# DRAM_DDR4.net
KiCad netlist of a schematic drawn in Altium Designer
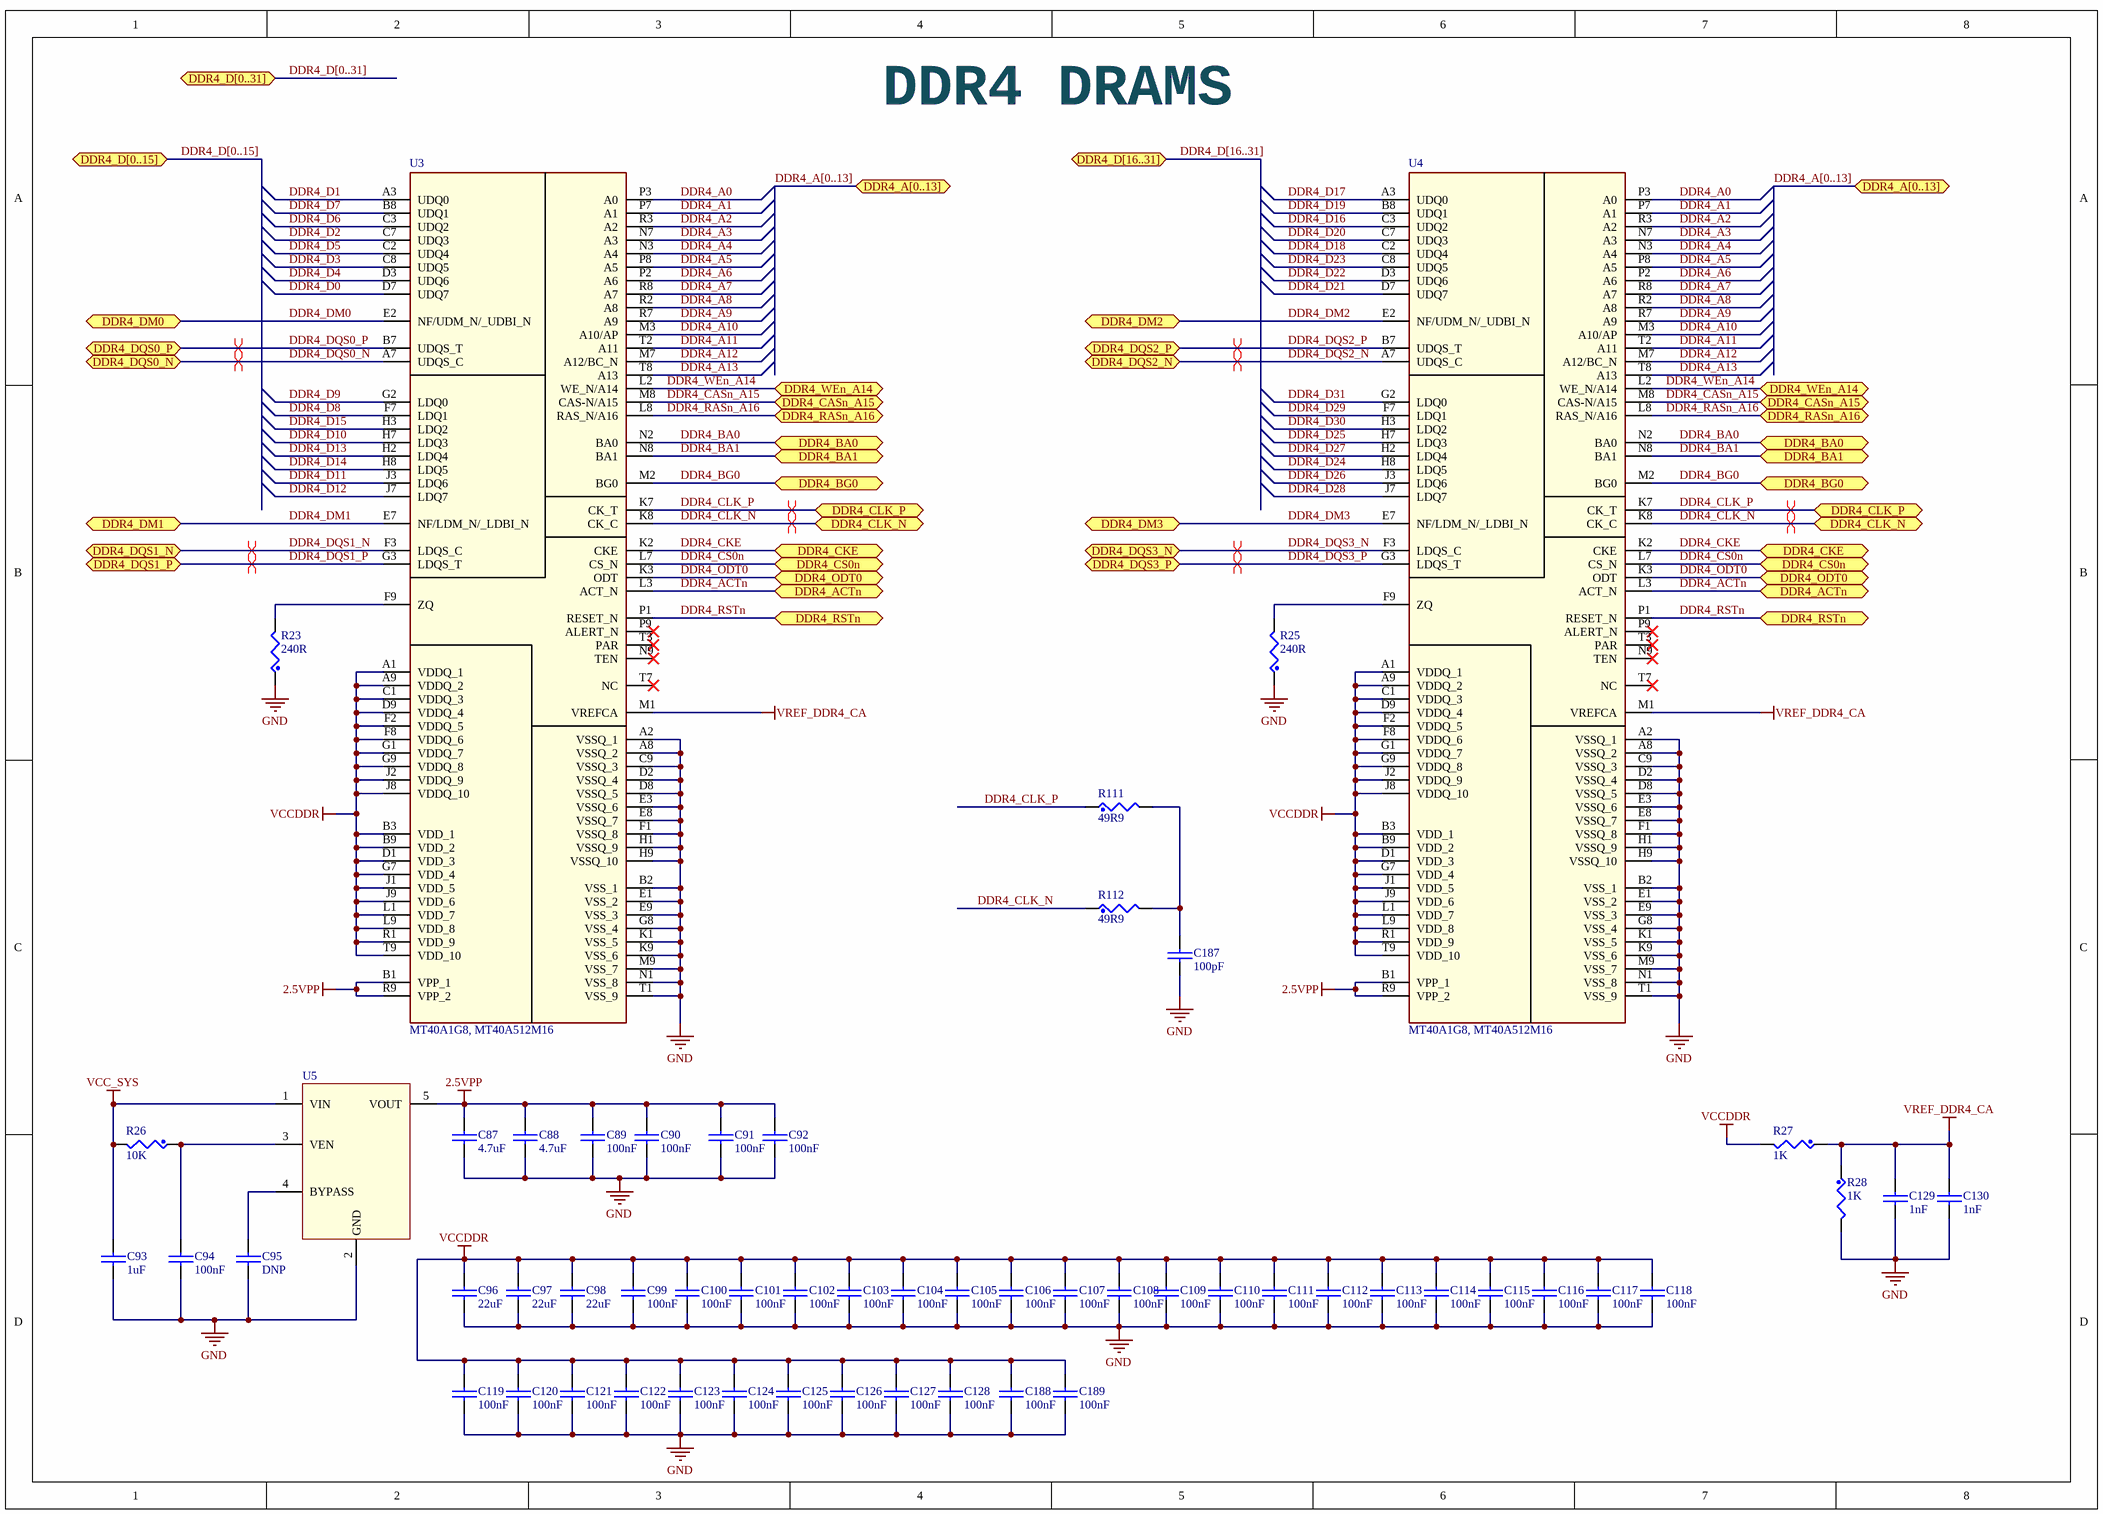
[diagram p0: DRAM_DDR4.SchDoc]

(export (version "E")
  (design (tool "Eeschema 10.0.6"))
  (components
    (comp (ref "C87")
      (value "4.7uF")
      (footprint "0402_CC - C")
      (libsource (lib "AAR_RockChip_RK3328") (part "CAP_NP"))
    )
    (comp (ref "C88")
      (value "4.7uF")
      (footprint "0402_CC - C")
      (libsource (lib "AAR_RockChip_RK3328") (part "CAP_NP"))
    )
    (comp (ref "C89")
      (value "100nF")
      (footprint "0402_CC - C")
      (libsource (lib "AAR_RockChip_RK3328") (part "CAP_NP"))
    )
    (comp (ref "C90")
      (value "100nF")
      (footprint "0402_CC - C")
      (libsource (lib "AAR_RockChip_RK3328") (part "CAP_NP"))
    )
    (comp (ref "C91")
      (value "100nF")
      (footprint "0402_CC - C")
      (libsource (lib "AAR_RockChip_RK3328") (part "CAP_NP"))
    )
    (comp (ref "C92")
      (value "100nF")
      (footprint "0402_CC - C")
      (libsource (lib "AAR_RockChip_RK3328") (part "CAP_NP"))
    )
    (comp (ref "C93")
      (value "1uF")
      (footprint "0402_CC - C")
      (libsource (lib "AAR_RockChip_RK3328") (part "CAP_NP"))
    )
    (comp (ref "C94")
      (value "100nF")
      (footprint "0402_CC - C")
      (libsource (lib "AAR_RockChip_RK3328") (part "CAP_NP"))
    )
    (comp (ref "C95")
      (value "DNP")
      (footprint "0402_CC - C")
      (libsource (lib "AAR_RockChip_RK3328") (part "CAP_NP"))
    )
    (comp (ref "C96")
      (value "22uF")
      (footprint "0603_CC")
      (libsource (lib "AAR_RockChip_RK3328") (part "CAP_NP"))
    )
    (comp (ref "C97")
      (value "22uF")
      (footprint "0603_CC")
      (libsource (lib "AAR_RockChip_RK3328") (part "CAP_NP"))
    )
    (comp (ref "C98")
      (value "22uF")
      (footprint "0603_CC")
      (libsource (lib "AAR_RockChip_RK3328") (part "CAP_NP"))
    )
    (comp (ref "C99")
      (value "100nF")
      (footprint "0402_CC - C")
      (libsource (lib "AAR_RockChip_RK3328") (part "CAP_NP"))
    )
    (comp (ref "C100")
      (value "100nF")
      (footprint "0402_CC - C")
      (libsource (lib "AAR_RockChip_RK3328") (part "CAP_NP"))
    )
    (comp (ref "C101")
      (value "100nF")
      (footprint "0402_CC - C")
      (libsource (lib "AAR_RockChip_RK3328") (part "CAP_NP"))
    )
    (comp (ref "C102")
      (value "100nF")
      (footprint "0402_CC - C")
      (libsource (lib "AAR_RockChip_RK3328") (part "CAP_NP"))
    )
    (comp (ref "C103")
      (value "100nF")
      (footprint "0402_CC - C")
      (libsource (lib "AAR_RockChip_RK3328") (part "CAP_NP"))
    )
    (comp (ref "C104")
      (value "100nF")
      (footprint "0402_CC - C")
      (libsource (lib "AAR_RockChip_RK3328") (part "CAP_NP"))
    )
    (comp (ref "C105")
      (value "100nF")
      (footprint "0402_CC - C")
      (libsource (lib "AAR_RockChip_RK3328") (part "CAP_NP"))
    )
    (comp (ref "C106")
      (value "100nF")
      (footprint "0402_CC - C")
      (libsource (lib "AAR_RockChip_RK3328") (part "CAP_NP"))
    )
    (comp (ref "C107")
      (value "100nF")
      (footprint "0402_CC - C")
      (libsource (lib "AAR_RockChip_RK3328") (part "CAP_NP"))
    )
    (comp (ref "C108")
      (value "100nF")
      (footprint "0402_CC - C")
      (libsource (lib "AAR_RockChip_RK3328") (part "CAP_NP"))
    )
    (comp (ref "C109")
      (value "100nF")
      (footprint "0402_CC - C")
      (libsource (lib "AAR_RockChip_RK3328") (part "CAP_NP"))
    )
    (comp (ref "C110")
      (value "100nF")
      (footprint "0402_CC - C")
      (libsource (lib "AAR_RockChip_RK3328") (part "CAP_NP"))
    )
    (comp (ref "C111")
      (value "100nF")
      (footprint "0402_CC - C")
      (libsource (lib "AAR_RockChip_RK3328") (part "CAP_NP"))
    )
    (comp (ref "C112")
      (value "100nF")
      (footprint "0402_CC - C")
      (libsource (lib "AAR_RockChip_RK3328") (part "CAP_NP"))
    )
    (comp (ref "C113")
      (value "100nF")
      (footprint "0402_CC - C")
      (libsource (lib "AAR_RockChip_RK3328") (part "CAP_NP"))
    )
    (comp (ref "C114")
      (value "100nF")
      (footprint "0402_CC - C")
      (libsource (lib "AAR_RockChip_RK3328") (part "CAP_NP"))
    )
    (comp (ref "C115")
      (value "100nF")
      (footprint "0402_CC - C")
      (libsource (lib "AAR_RockChip_RK3328") (part "CAP_NP"))
    )
    (comp (ref "C116")
      (value "100nF")
      (footprint "0402_CC - C")
      (libsource (lib "AAR_RockChip_RK3328") (part "CAP_NP"))
    )
    (comp (ref "C117")
      (value "100nF")
      (footprint "0402_CC - C")
      (libsource (lib "AAR_RockChip_RK3328") (part "CAP_NP"))
    )
    (comp (ref "C118")
      (value "100nF")
      (footprint "0402_CC - C")
      (libsource (lib "AAR_RockChip_RK3328") (part "CAP_NP"))
    )
    (comp (ref "C119")
      (value "100nF")
      (footprint "0402_CC - C")
      (libsource (lib "AAR_RockChip_RK3328") (part "CAP_NP"))
    )
    (comp (ref "C120")
      (value "100nF")
      (footprint "0402_CC - C")
      (libsource (lib "AAR_RockChip_RK3328") (part "CAP_NP"))
    )
    (comp (ref "C121")
      (value "100nF")
      (footprint "0402_CC - C")
      (libsource (lib "AAR_RockChip_RK3328") (part "CAP_NP"))
    )
    (comp (ref "C122")
      (value "100nF")
      (footprint "0402_CC - C")
      (libsource (lib "AAR_RockChip_RK3328") (part "CAP_NP"))
    )
    (comp (ref "C123")
      (value "100nF")
      (footprint "0402_CC - C")
      (libsource (lib "AAR_RockChip_RK3328") (part "CAP_NP"))
    )
    (comp (ref "C124")
      (value "100nF")
      (footprint "0402_CC - C")
      (libsource (lib "AAR_RockChip_RK3328") (part "CAP_NP"))
    )
    (comp (ref "C125")
      (value "100nF")
      (footprint "0402_CC - C")
      (libsource (lib "AAR_RockChip_RK3328") (part "CAP_NP"))
    )
    (comp (ref "C126")
      (value "100nF")
      (footprint "0402_CC - C")
      (libsource (lib "AAR_RockChip_RK3328") (part "CAP_NP"))
    )
    (comp (ref "C127")
      (value "100nF")
      (footprint "0402_CC - C")
      (libsource (lib "AAR_RockChip_RK3328") (part "CAP_NP"))
    )
    (comp (ref "C128")
      (value "100nF")
      (footprint "0402_CC - C")
      (libsource (lib "AAR_RockChip_RK3328") (part "CAP_NP"))
    )
    (comp (ref "C129")
      (value "1nF")
      (footprint "0402_CC - C")
      (libsource (lib "AAR_RockChip_RK3328") (part "CAP_NP"))
    )
    (comp (ref "C130")
      (value "1nF")
      (footprint "0402_CC - C")
      (libsource (lib "AAR_RockChip_RK3328") (part "CAP_NP"))
    )
    (comp (ref "C187")
      (value "100pF")
      (footprint "0402_CC - C")
      (libsource (lib "AAR_RockChip_RK3328") (part "CAP_NP"))
    )
    (comp (ref "C188")
      (value "100nF")
      (footprint "0402_CC - C")
      (libsource (lib "AAR_RockChip_RK3328") (part "CAP_NP"))
    )
    (comp (ref "C189")
      (value "100nF")
      (footprint "0402_CC - C")
      (libsource (lib "AAR_RockChip_RK3328") (part "CAP_NP"))
    )
    (comp (ref "R23")
      (value "240R")
      (footprint "0402_CR")
      (libsource (lib "AAR_RockChip_RK3328") (part "RES"))
    )
    (comp (ref "R25")
      (value "240R")
      (footprint "0402_CR")
      (libsource (lib "AAR_RockChip_RK3328") (part "RES"))
    )
    (comp (ref "R26")
      (value "10K")
      (footprint "0402_CR")
      (libsource (lib "AAR_RockChip_RK3328") (part "RES"))
    )
    (comp (ref "R27") (value "1K") (footprint "0603_CR") (libsource (lib "AAR_RockChip_RK3328") (part "RES")))
    (comp (ref "R28") (value "1K") (footprint "0603_CR") (libsource (lib "AAR_RockChip_RK3328") (part "RES")))
    (comp (ref "R111")
      (value "49R9")
      (footprint "0402_CR")
      (libsource (lib "AAR_RockChip_RK3328") (part "RES"))
    )
    (comp (ref "R112")
      (value "49R9")
      (footprint "0402_CR")
      (libsource (lib "AAR_RockChip_RK3328") (part "RES"))
    )
    (comp (ref "U3")
      (value "MT40A1G8, MT40A512M16")
      (footprint "BGA96C80P9X16_1000X1400X120")
      (description "AAR, MT40A, DDR4 , 96-Ball x16")
      (fields (field (name "MANUFACTURER_PART_NUMBER") "MT40A1G16HBA-083E"))
      (libsource (lib "AAR_RockChip_RK3328") (part "MT40A1G8"))
    )
    (comp (ref "U4")
      (value "MT40A1G8, MT40A512M16")
      (footprint "BGA96C80P9X16_1000X1400X120")
      (description "AAR, MT40A, DDR4 , 96-Ball x16")
      (fields (field (name "MANUFACTURER_PART_NUMBER") "MT40A1G16HBA-083E"))
      (libsource (lib "AAR_RockChip_RK3328") (part "MT40A1G8"))
    )
    (comp (ref "U5")
      (value "LDO")
      (footprint "SOT23_5")
      (description "PT5108  , High-PSRR 500mA LDO, By AAR")
      (libsource (lib "AAR_RockChip_RK3328") (part "PT5108"))
    )
  )
  (nets
    (net (code "1") (name "/DDR4_A0") (class "Default")
      (node (ref "U3") (pin "P3") (pinfunction "A0_P3") (pintype "passive"))
      (node (ref "U4") (pin "P3") (pinfunction "A0_P3") (pintype "passive"))
    )
    (net (code "2") (name "/DDR4_A1") (class "Default")
      (node (ref "U3") (pin "P7") (pinfunction "A1_P7") (pintype "passive"))
      (node (ref "U4") (pin "P7") (pinfunction "A1_P7") (pintype "passive"))
    )
    (net (code "3") (name "/DDR4_A2") (class "Default")
      (node (ref "U3") (pin "R3") (pinfunction "A2_R3") (pintype "passive"))
      (node (ref "U4") (pin "R3") (pinfunction "A2_R3") (pintype "passive"))
    )
    (net (code "4") (name "/DDR4_A3") (class "Default")
      (node (ref "U3") (pin "N7") (pinfunction "A3_N7") (pintype "passive"))
      (node (ref "U4") (pin "N7") (pinfunction "A3_N7") (pintype "passive"))
    )
    (net (code "5") (name "/DDR4_A4") (class "Default")
      (node (ref "U3") (pin "N3") (pinfunction "A4_N3") (pintype "passive"))
      (node (ref "U4") (pin "N3") (pinfunction "A4_N3") (pintype "passive"))
    )
    (net (code "6") (name "/DDR4_A5") (class "Default")
      (node (ref "U3") (pin "P8") (pinfunction "A5_P8") (pintype "passive"))
      (node (ref "U4") (pin "P8") (pinfunction "A5_P8") (pintype "passive"))
    )
    (net (code "7") (name "/DDR4_A6") (class "Default")
      (node (ref "U3") (pin "P2") (pinfunction "A6_P2") (pintype "passive"))
      (node (ref "U4") (pin "P2") (pinfunction "A6_P2") (pintype "passive"))
    )
    (net (code "8") (name "/DDR4_A7") (class "Default")
      (node (ref "U3") (pin "R8") (pinfunction "A7_R8") (pintype "passive"))
      (node (ref "U4") (pin "R8") (pinfunction "A7_R8") (pintype "passive"))
    )
    (net (code "9") (name "/DDR4_A8") (class "Default")
      (node (ref "U3") (pin "R2") (pinfunction "A8_R2") (pintype "passive"))
      (node (ref "U4") (pin "R2") (pinfunction "A8_R2") (pintype "passive"))
    )
    (net (code "10") (name "/DDR4_A9") (class "Default")
      (node (ref "U3") (pin "R7") (pinfunction "A9_R7") (pintype "passive"))
      (node (ref "U4") (pin "R7") (pinfunction "A9_R7") (pintype "passive"))
    )
    (net (code "11") (name "/DDR4_A10") (class "Default")
      (node (ref "U3") (pin "M3") (pinfunction "A10/AP_M3") (pintype "passive"))
      (node (ref "U4") (pin "M3") (pinfunction "A10/AP_M3") (pintype "passive"))
    )
    (net (code "12") (name "/DDR4_A11") (class "Default")
      (node (ref "U3") (pin "T2") (pinfunction "A11_T2") (pintype "passive"))
      (node (ref "U4") (pin "T2") (pinfunction "A11_T2") (pintype "passive"))
    )
    (net (code "13") (name "/DDR4_A12") (class "Default")
      (node (ref "U3") (pin "M7") (pinfunction "A12/BC_N_M7") (pintype "passive"))
      (node (ref "U4") (pin "M7") (pinfunction "A12/BC_N_M7") (pintype "passive"))
    )
    (net (code "14") (name "/DDR4_A13") (class "Default")
      (node (ref "U3") (pin "T8") (pinfunction "A13_T8") (pintype "passive"))
      (node (ref "U4") (pin "T8") (pinfunction "A13_T8") (pintype "passive"))
    )
    (net (code "15") (name "/DDR4_ACTn") (class "Default")
      (node (ref "U3") (pin "L3") (pinfunction "ACT_N_L3") (pintype "passive"))
      (node (ref "U4") (pin "L3") (pinfunction "ACT_N_L3") (pintype "passive"))
    )
    (net (code "17") (name "/DDR4_BA0") (class "Default")
      (node (ref "U3") (pin "N2") (pinfunction "BA0_N2") (pintype "passive"))
      (node (ref "U4") (pin "N2") (pinfunction "BA0_N2") (pintype "passive"))
    )
    (net (code "18") (name "/DDR4_BA1") (class "Default")
      (node (ref "U3") (pin "N8") (pinfunction "BA1_N8") (pintype "passive"))
      (node (ref "U4") (pin "N8") (pinfunction "BA1_N8") (pintype "passive"))
    )
    (net (code "19") (name "/DDR4_BG0") (class "Default")
      (node (ref "U3") (pin "M2") (pinfunction "BG0_M2") (pintype "passive"))
      (node (ref "U4") (pin "M2") (pinfunction "BG0_M2") (pintype "passive"))
    )
    (net (code "20") (name "/DDR4_CASn_A15") (class "Default")
      (node (ref "U3") (pin "M8") (pinfunction "CAS-N/A15_M8") (pintype "passive"))
      (node (ref "U4") (pin "M8") (pinfunction "CAS-N/A15_M8") (pintype "passive"))
    )
    (net (code "21") (name "/DDR4_CKE") (class "Default")
      (node (ref "U3") (pin "K2") (pinfunction "CKE_K2") (pintype "passive"))
      (node (ref "U4") (pin "K2") (pinfunction "CKE_K2") (pintype "passive"))
    )
    (net (code "22") (name "/DDR4_CLK_N") (class "Default")
      (node (ref "R112") (pin "1") (pinfunction "1_1") (pintype "passive"))
      (node (ref "U3") (pin "K8") (pinfunction "CK_C_K8") (pintype "passive"))
      (node (ref "U4") (pin "K8") (pinfunction "CK_C_K8") (pintype "passive"))
    )
    (net (code "23") (name "/DDR4_CLK_P") (class "Default")
      (node (ref "R111") (pin "1") (pinfunction "1_1") (pintype "passive"))
      (node (ref "U3") (pin "K7") (pinfunction "CK_T_K7") (pintype "passive"))
      (node (ref "U4") (pin "K7") (pinfunction "CK_T_K7") (pintype "passive"))
    )
    (net (code "24") (name "/DDR4_CS0n") (class "Default")
      (node (ref "U3") (pin "L7") (pinfunction "CS_N_L7") (pintype "passive"))
      (node (ref "U4") (pin "L7") (pinfunction "CS_N_L7") (pintype "passive"))
    )
    (net (code "25") (name "/DDR4_D0") (class "Default")
      (node (ref "U3") (pin "D7") (pinfunction "UDQ7_D7") (pintype "passive"))
    )
    (net (code "26") (name "/DDR4_D1") (class "Default")
      (node (ref "U3") (pin "A3") (pinfunction "UDQ0_A3") (pintype "passive"))
    )
    (net (code "27") (name "/DDR4_D2") (class "Default")
      (node (ref "U3") (pin "C7") (pinfunction "UDQ3_C7") (pintype "passive"))
    )
    (net (code "28") (name "/DDR4_D3") (class "Default")
      (node (ref "U3") (pin "C8") (pinfunction "UDQ5_C8") (pintype "passive"))
    )
    (net (code "29") (name "/DDR4_D4") (class "Default")
      (node (ref "U3") (pin "D3") (pinfunction "UDQ6_D3") (pintype "passive"))
    )
    (net (code "30") (name "/DDR4_D5") (class "Default")
      (node (ref "U3") (pin "C2") (pinfunction "UDQ4_C2") (pintype "passive"))
    )
    (net (code "31") (name "/DDR4_D6") (class "Default")
      (node (ref "U3") (pin "C3") (pinfunction "UDQ2_C3") (pintype "passive"))
    )
    (net (code "32") (name "/DDR4_D7") (class "Default")
      (node (ref "U3") (pin "B8") (pinfunction "UDQ1_B8") (pintype "passive"))
    )
    (net (code "33") (name "/DDR4_D8") (class "Default")
      (node (ref "U3") (pin "F7") (pinfunction "LDQ1_F7") (pintype "passive"))
    )
    (net (code "34") (name "/DDR4_D9") (class "Default")
      (node (ref "U3") (pin "G2") (pinfunction "LDQ0_G2") (pintype "passive"))
    )
    (net (code "35") (name "/DDR4_D10") (class "Default")
      (node (ref "U3") (pin "H7") (pinfunction "LDQ3_H7") (pintype "passive"))
    )
    (net (code "36") (name "/DDR4_D11") (class "Default")
      (node (ref "U3") (pin "J3") (pinfunction "LDQ6_J3") (pintype "passive"))
    )
    (net (code "37") (name "/DDR4_D12") (class "Default")
      (node (ref "U3") (pin "J7") (pinfunction "LDQ7_J7") (pintype "passive"))
    )
    (net (code "38") (name "/DDR4_D13") (class "Default")
      (node (ref "U3") (pin "H2") (pinfunction "LDQ4_H2") (pintype "passive"))
    )
    (net (code "39") (name "/DDR4_D14") (class "Default")
      (node (ref "U3") (pin "H8") (pinfunction "LDQ5_H8") (pintype "passive"))
    )
    (net (code "40") (name "/DDR4_D15") (class "Default")
      (node (ref "U3") (pin "H3") (pinfunction "LDQ2_H3") (pintype "passive"))
    )
    (net (code "41") (name "/DDR4_D16") (class "Default")
      (node (ref "U4") (pin "C3") (pinfunction "UDQ2_C3") (pintype "passive"))
    )
    (net (code "42") (name "/DDR4_D17") (class "Default")
      (node (ref "U4") (pin "A3") (pinfunction "UDQ0_A3") (pintype "passive"))
    )
    (net (code "43") (name "/DDR4_D18") (class "Default")
      (node (ref "U4") (pin "C2") (pinfunction "UDQ4_C2") (pintype "passive"))
    )
    (net (code "44") (name "/DDR4_D19") (class "Default")
      (node (ref "U4") (pin "B8") (pinfunction "UDQ1_B8") (pintype "passive"))
    )
    (net (code "45") (name "/DDR4_D20") (class "Default")
      (node (ref "U4") (pin "C7") (pinfunction "UDQ3_C7") (pintype "passive"))
    )
    (net (code "46") (name "/DDR4_D21") (class "Default")
      (node (ref "U4") (pin "D7") (pinfunction "UDQ7_D7") (pintype "passive"))
    )
    (net (code "47") (name "/DDR4_D22") (class "Default")
      (node (ref "U4") (pin "D3") (pinfunction "UDQ6_D3") (pintype "passive"))
    )
    (net (code "48") (name "/DDR4_D23") (class "Default")
      (node (ref "U4") (pin "C8") (pinfunction "UDQ5_C8") (pintype "passive"))
    )
    (net (code "49") (name "/DDR4_D24") (class "Default")
      (node (ref "U4") (pin "H8") (pinfunction "LDQ5_H8") (pintype "passive"))
    )
    (net (code "50") (name "/DDR4_D25") (class "Default")
      (node (ref "U4") (pin "H7") (pinfunction "LDQ3_H7") (pintype "passive"))
    )
    (net (code "51") (name "/DDR4_D26") (class "Default")
      (node (ref "U4") (pin "J3") (pinfunction "LDQ6_J3") (pintype "passive"))
    )
    (net (code "52") (name "/DDR4_D27") (class "Default")
      (node (ref "U4") (pin "H2") (pinfunction "LDQ4_H2") (pintype "passive"))
    )
    (net (code "53") (name "/DDR4_D28") (class "Default")
      (node (ref "U4") (pin "J7") (pinfunction "LDQ7_J7") (pintype "passive"))
    )
    (net (code "54") (name "/DDR4_D29") (class "Default")
      (node (ref "U4") (pin "F7") (pinfunction "LDQ1_F7") (pintype "passive"))
    )
    (net (code "55") (name "/DDR4_D30") (class "Default")
      (node (ref "U4") (pin "H3") (pinfunction "LDQ2_H3") (pintype "passive"))
    )
    (net (code "56") (name "/DDR4_D31") (class "Default")
      (node (ref "U4") (pin "G2") (pinfunction "LDQ0_G2") (pintype "passive"))
    )
    (net (code "57") (name "/DDR4_DM0") (class "Default")
      (node (ref "U3") (pin "E2") (pinfunction "NF/UDM_N/_UDBI_N_E2") (pintype "passive"))
    )
    (net (code "58") (name "/DDR4_DM1") (class "Default")
      (node (ref "U3") (pin "E7") (pinfunction "NF/LDM_N/_LDBI_N_E7") (pintype "passive"))
    )
    (net (code "59") (name "/DDR4_DM2") (class "Default")
      (node (ref "U4") (pin "E2") (pinfunction "NF/UDM_N/_UDBI_N_E2") (pintype "passive"))
    )
    (net (code "60") (name "/DDR4_DM3") (class "Default")
      (node (ref "U4") (pin "E7") (pinfunction "NF/LDM_N/_LDBI_N_E7") (pintype "passive"))
    )
    (net (code "61") (name "/DDR4_DQS0_N") (class "Default")
      (node (ref "U3") (pin "A7") (pinfunction "UDQS_C_A7") (pintype "passive"))
    )
    (net (code "62") (name "/DDR4_DQS0_P") (class "Default")
      (node (ref "U3") (pin "B7") (pinfunction "UDQS_T_B7") (pintype "passive"))
    )
    (net (code "63") (name "/DDR4_DQS1_N") (class "Default")
      (node (ref "U3") (pin "F3") (pinfunction "LDQS_C_F3") (pintype "passive"))
    )
    (net (code "64") (name "/DDR4_DQS1_P") (class "Default")
      (node (ref "U3") (pin "G3") (pinfunction "LDQS_T_G3") (pintype "passive"))
    )
    (net (code "65") (name "/DDR4_DQS2_N") (class "Default")
      (node (ref "U4") (pin "A7") (pinfunction "UDQS_C_A7") (pintype "passive"))
    )
    (net (code "66") (name "/DDR4_DQS2_P") (class "Default")
      (node (ref "U4") (pin "B7") (pinfunction "UDQS_T_B7") (pintype "passive"))
    )
    (net (code "67") (name "/DDR4_DQS3_N") (class "Default")
      (node (ref "U4") (pin "F3") (pinfunction "LDQS_C_F3") (pintype "passive"))
    )
    (net (code "68") (name "/DDR4_DQS3_P") (class "Default")
      (node (ref "U4") (pin "G3") (pinfunction "LDQS_T_G3") (pintype "passive"))
    )
    (net (code "72") (name "/DDR4_ODT0") (class "Default")
      (node (ref "U3") (pin "K3") (pinfunction "ODT_K3") (pintype "passive"))
      (node (ref "U4") (pin "K3") (pinfunction "ODT_K3") (pintype "passive"))
    )
    (net (code "73") (name "/DDR4_RASn_A16") (class "Default")
      (node (ref "U3") (pin "L8") (pinfunction "RAS_N/A16_L8") (pintype "passive"))
      (node (ref "U4") (pin "L8") (pinfunction "RAS_N/A16_L8") (pintype "passive"))
    )
    (net (code "74") (name "/DDR4_RSTn") (class "Default")
      (node (ref "U3") (pin "P1") (pinfunction "RESET_N_P1") (pintype "passive"))
      (node (ref "U4") (pin "P1") (pinfunction "RESET_N_P1") (pintype "passive"))
    )
    (net (code "75") (name "/DDR4_WEn_A14") (class "Default")
      (node (ref "U3") (pin "L2") (pinfunction "WE_N/A14_L2") (pintype "passive"))
      (node (ref "U4") (pin "L2") (pinfunction "WE_N/A14_L2") (pintype "passive"))
    )
    (net (code "76") (name "2.5VPP") (class "Default")
      (node (ref "C87") (pin "1") (pinfunction "1_1") (pintype "passive"))
      (node (ref "C88") (pin "1") (pinfunction "1_1") (pintype "passive"))
      (node (ref "C89") (pin "1") (pinfunction "1_1") (pintype "passive"))
      (node (ref "C90") (pin "1") (pinfunction "1_1") (pintype "passive"))
      (node (ref "C91") (pin "1") (pinfunction "1_1") (pintype "passive"))
      (node (ref "C92") (pin "1") (pinfunction "1_1") (pintype "passive"))
      (node (ref "U3") (pin "B1") (pinfunction "VPP_1_B1") (pintype "power_in"))
      (node (ref "U3") (pin "R9") (pinfunction "VPP_2_R9") (pintype "power_in"))
      (node (ref "U4") (pin "B1") (pinfunction "VPP_1_B1") (pintype "power_in"))
      (node (ref "U4") (pin "R9") (pinfunction "VPP_2_R9") (pintype "power_in"))
      (node (ref "U5") (pin "5") (pinfunction "VOUT_5") (pintype "power_in"))
    )
    (net (code "77") (name "GND") (class "Default")
      (node (ref "C100") (pin "2") (pinfunction "2_2") (pintype "passive"))
      (node (ref "C101") (pin "2") (pinfunction "2_2") (pintype "passive"))
      (node (ref "C102") (pin "2") (pinfunction "2_2") (pintype "passive"))
      (node (ref "C103") (pin "2") (pinfunction "2_2") (pintype "passive"))
      (node (ref "C104") (pin "2") (pinfunction "2_2") (pintype "passive"))
      (node (ref "C105") (pin "2") (pinfunction "2_2") (pintype "passive"))
      (node (ref "C106") (pin "2") (pinfunction "2_2") (pintype "passive"))
      (node (ref "C107") (pin "2") (pinfunction "2_2") (pintype "passive"))
      (node (ref "C108") (pin "2") (pinfunction "2_2") (pintype "passive"))
      (node (ref "C109") (pin "2") (pinfunction "2_2") (pintype "passive"))
      (node (ref "C110") (pin "2") (pinfunction "2_2") (pintype "passive"))
      (node (ref "C111") (pin "2") (pinfunction "2_2") (pintype "passive"))
      (node (ref "C112") (pin "2") (pinfunction "2_2") (pintype "passive"))
      (node (ref "C113") (pin "2") (pinfunction "2_2") (pintype "passive"))
      (node (ref "C114") (pin "2") (pinfunction "2_2") (pintype "passive"))
      (node (ref "C115") (pin "2") (pinfunction "2_2") (pintype "passive"))
      (node (ref "C116") (pin "2") (pinfunction "2_2") (pintype "passive"))
      (node (ref "C117") (pin "2") (pinfunction "2_2") (pintype "passive"))
      (node (ref "C118") (pin "2") (pinfunction "2_2") (pintype "passive"))
      (node (ref "C119") (pin "2") (pinfunction "2_2") (pintype "passive"))
      (node (ref "C120") (pin "2") (pinfunction "2_2") (pintype "passive"))
      (node (ref "C121") (pin "2") (pinfunction "2_2") (pintype "passive"))
      (node (ref "C122") (pin "2") (pinfunction "2_2") (pintype "passive"))
      (node (ref "C123") (pin "2") (pinfunction "2_2") (pintype "passive"))
      (node (ref "C124") (pin "2") (pinfunction "2_2") (pintype "passive"))
      (node (ref "C125") (pin "2") (pinfunction "2_2") (pintype "passive"))
      (node (ref "C126") (pin "2") (pinfunction "2_2") (pintype "passive"))
      (node (ref "C127") (pin "2") (pinfunction "2_2") (pintype "passive"))
      (node (ref "C128") (pin "2") (pinfunction "2_2") (pintype "passive"))
      (node (ref "C129") (pin "2") (pinfunction "2_2") (pintype "passive"))
      (node (ref "C130") (pin "2") (pinfunction "2_2") (pintype "passive"))
      (node (ref "C187") (pin "2") (pinfunction "2_2") (pintype "passive"))
      (node (ref "C188") (pin "2") (pinfunction "2_2") (pintype "passive"))
      (node (ref "C189") (pin "2") (pinfunction "2_2") (pintype "passive"))
      (node (ref "C87") (pin "2") (pinfunction "2_2") (pintype "passive"))
      (node (ref "C88") (pin "2") (pinfunction "2_2") (pintype "passive"))
      (node (ref "C89") (pin "2") (pinfunction "2_2") (pintype "passive"))
      (node (ref "C90") (pin "2") (pinfunction "2_2") (pintype "passive"))
      (node (ref "C91") (pin "2") (pinfunction "2_2") (pintype "passive"))
      (node (ref "C92") (pin "2") (pinfunction "2_2") (pintype "passive"))
      (node (ref "C93") (pin "2") (pinfunction "2_2") (pintype "passive"))
      (node (ref "C94") (pin "2") (pinfunction "2_2") (pintype "passive"))
      (node (ref "C95") (pin "2") (pinfunction "2_2") (pintype "passive"))
      (node (ref "C96") (pin "2") (pinfunction "2_2") (pintype "passive"))
      (node (ref "C97") (pin "2") (pinfunction "2_2") (pintype "passive"))
      (node (ref "C98") (pin "2") (pinfunction "2_2") (pintype "passive"))
      (node (ref "C99") (pin "2") (pinfunction "2_2") (pintype "passive"))
      (node (ref "R23") (pin "1") (pinfunction "1_1") (pintype "passive"))
      (node (ref "R25") (pin "1") (pinfunction "1_1") (pintype "passive"))
      (node (ref "R28") (pin "2") (pinfunction "2_2") (pintype "passive"))
      (node (ref "U3") (pin "A2") (pinfunction "VSSQ_1_A2") (pintype "power_in"))
      (node (ref "U3") (pin "A8") (pinfunction "VSSQ_2_A8") (pintype "power_in"))
      (node (ref "U3") (pin "B2") (pinfunction "VSS_1_B2") (pintype "power_in"))
      (node (ref "U3") (pin "C9") (pinfunction "VSSQ_3_C9") (pintype "power_in"))
      (node (ref "U3") (pin "D2") (pinfunction "VSSQ_4_D2") (pintype "power_in"))
      (node (ref "U3") (pin "D8") (pinfunction "VSSQ_5_D8") (pintype "power_in"))
      (node (ref "U3") (pin "E1") (pinfunction "VSS_2_E1") (pintype "power_in"))
      (node (ref "U3") (pin "E3") (pinfunction "VSSQ_6_E3") (pintype "power_in"))
      (node (ref "U3") (pin "E8") (pinfunction "VSSQ_7_E8") (pintype "power_in"))
      (node (ref "U3") (pin "E9") (pinfunction "VSS_3_E9") (pintype "power_in"))
      (node (ref "U3") (pin "F1") (pinfunction "VSSQ_8_F1") (pintype "power_in"))
      (node (ref "U3") (pin "G8") (pinfunction "VSS_4_G8") (pintype "power_in"))
      (node (ref "U3") (pin "H1") (pinfunction "VSSQ_9_H1") (pintype "power_in"))
      (node (ref "U3") (pin "H9") (pinfunction "VSSQ_10_H9") (pintype "power_in"))
      (node (ref "U3") (pin "K1") (pinfunction "VSS_5_K1") (pintype "power_in"))
      (node (ref "U3") (pin "K9") (pinfunction "VSS_6_K9") (pintype "power_in"))
      (node (ref "U3") (pin "M9") (pinfunction "VSS_7_M9") (pintype "power_in"))
      (node (ref "U3") (pin "N1") (pinfunction "VSS_8_N1") (pintype "power_in"))
      (node (ref "U3") (pin "T1") (pinfunction "VSS_9_T1") (pintype "power_in"))
      (node (ref "U4") (pin "A2") (pinfunction "VSSQ_1_A2") (pintype "power_in"))
      (node (ref "U4") (pin "A8") (pinfunction "VSSQ_2_A8") (pintype "power_in"))
      (node (ref "U4") (pin "B2") (pinfunction "VSS_1_B2") (pintype "power_in"))
      (node (ref "U4") (pin "C9") (pinfunction "VSSQ_3_C9") (pintype "power_in"))
      (node (ref "U4") (pin "D2") (pinfunction "VSSQ_4_D2") (pintype "power_in"))
      (node (ref "U4") (pin "D8") (pinfunction "VSSQ_5_D8") (pintype "power_in"))
      (node (ref "U4") (pin "E1") (pinfunction "VSS_2_E1") (pintype "power_in"))
      (node (ref "U4") (pin "E3") (pinfunction "VSSQ_6_E3") (pintype "power_in"))
      (node (ref "U4") (pin "E8") (pinfunction "VSSQ_7_E8") (pintype "power_in"))
      (node (ref "U4") (pin "E9") (pinfunction "VSS_3_E9") (pintype "power_in"))
      (node (ref "U4") (pin "F1") (pinfunction "VSSQ_8_F1") (pintype "power_in"))
      (node (ref "U4") (pin "G8") (pinfunction "VSS_4_G8") (pintype "power_in"))
      (node (ref "U4") (pin "H1") (pinfunction "VSSQ_9_H1") (pintype "power_in"))
      (node (ref "U4") (pin "H9") (pinfunction "VSSQ_10_H9") (pintype "power_in"))
      (node (ref "U4") (pin "K1") (pinfunction "VSS_5_K1") (pintype "power_in"))
      (node (ref "U4") (pin "K9") (pinfunction "VSS_6_K9") (pintype "power_in"))
      (node (ref "U4") (pin "M9") (pinfunction "VSS_7_M9") (pintype "power_in"))
      (node (ref "U4") (pin "N1") (pinfunction "VSS_8_N1") (pintype "power_in"))
      (node (ref "U4") (pin "T1") (pinfunction "VSS_9_T1") (pintype "power_in"))
      (node (ref "U5") (pin "2") (pinfunction "GND_2") (pintype "power_in"))
    )
    (net (code "78") (name "Net-(C187-Pad1)") (class "Default")
      (node (ref "C187") (pin "1") (pinfunction "1_1") (pintype "passive"))
      (node (ref "R111") (pin "2") (pinfunction "2_2") (pintype "passive"))
      (node (ref "R112") (pin "2") (pinfunction "2_2") (pintype "passive"))
    )
    (net (code "79") (name "Net-(U3-ZQ)") (class "Default")
      (node (ref "R23") (pin "2") (pinfunction "2_2") (pintype "passive"))
      (node (ref "U3") (pin "F9") (pinfunction "ZQ_F9") (pintype "passive"))
    )
    (net (code "80") (name "Net-(U4-ZQ)") (class "Default")
      (node (ref "R25") (pin "2") (pinfunction "2_2") (pintype "passive"))
      (node (ref "U4") (pin "F9") (pinfunction "ZQ_F9") (pintype "passive"))
    )
    (net (code "81") (name "Net-(U5-BYPASS)") (class "Default")
      (node (ref "C95") (pin "1") (pinfunction "1_1") (pintype "passive"))
      (node (ref "U5") (pin "4") (pinfunction "BYPASS_4") (pintype "power_in"))
    )
    (net (code "82") (name "Net-(U5-VEN)") (class "Default")
      (node (ref "C94") (pin "1") (pinfunction "1_1") (pintype "passive"))
      (node (ref "R26") (pin "1") (pinfunction "1_1") (pintype "passive"))
      (node (ref "U5") (pin "3") (pinfunction "VEN_3") (pintype "power_in"))
    )
    (net (code "83") (name "VCCDDR") (class "Default")
      (node (ref "C100") (pin "1") (pinfunction "1_1") (pintype "passive"))
      (node (ref "C101") (pin "1") (pinfunction "1_1") (pintype "passive"))
      (node (ref "C102") (pin "1") (pinfunction "1_1") (pintype "passive"))
      (node (ref "C103") (pin "1") (pinfunction "1_1") (pintype "passive"))
      (node (ref "C104") (pin "1") (pinfunction "1_1") (pintype "passive"))
      (node (ref "C105") (pin "1") (pinfunction "1_1") (pintype "passive"))
      (node (ref "C106") (pin "1") (pinfunction "1_1") (pintype "passive"))
      (node (ref "C107") (pin "1") (pinfunction "1_1") (pintype "passive"))
      (node (ref "C108") (pin "1") (pinfunction "1_1") (pintype "passive"))
      (node (ref "C109") (pin "1") (pinfunction "1_1") (pintype "passive"))
      (node (ref "C110") (pin "1") (pinfunction "1_1") (pintype "passive"))
      (node (ref "C111") (pin "1") (pinfunction "1_1") (pintype "passive"))
      (node (ref "C112") (pin "1") (pinfunction "1_1") (pintype "passive"))
      (node (ref "C113") (pin "1") (pinfunction "1_1") (pintype "passive"))
      (node (ref "C114") (pin "1") (pinfunction "1_1") (pintype "passive"))
      (node (ref "C115") (pin "1") (pinfunction "1_1") (pintype "passive"))
      (node (ref "C116") (pin "1") (pinfunction "1_1") (pintype "passive"))
      (node (ref "C117") (pin "1") (pinfunction "1_1") (pintype "passive"))
      (node (ref "C118") (pin "1") (pinfunction "1_1") (pintype "passive"))
      (node (ref "C119") (pin "1") (pinfunction "1_1") (pintype "passive"))
      (node (ref "C120") (pin "1") (pinfunction "1_1") (pintype "passive"))
      (node (ref "C121") (pin "1") (pinfunction "1_1") (pintype "passive"))
      (node (ref "C122") (pin "1") (pinfunction "1_1") (pintype "passive"))
      (node (ref "C123") (pin "1") (pinfunction "1_1") (pintype "passive"))
      (node (ref "C124") (pin "1") (pinfunction "1_1") (pintype "passive"))
      (node (ref "C125") (pin "1") (pinfunction "1_1") (pintype "passive"))
      (node (ref "C126") (pin "1") (pinfunction "1_1") (pintype "passive"))
      (node (ref "C127") (pin "1") (pinfunction "1_1") (pintype "passive"))
      (node (ref "C128") (pin "1") (pinfunction "1_1") (pintype "passive"))
      (node (ref "C188") (pin "1") (pinfunction "1_1") (pintype "passive"))
      (node (ref "C189") (pin "1") (pinfunction "1_1") (pintype "passive"))
      (node (ref "C96") (pin "1") (pinfunction "1_1") (pintype "passive"))
      (node (ref "C97") (pin "1") (pinfunction "1_1") (pintype "passive"))
      (node (ref "C98") (pin "1") (pinfunction "1_1") (pintype "passive"))
      (node (ref "C99") (pin "1") (pinfunction "1_1") (pintype "passive"))
      (node (ref "R27") (pin "2") (pinfunction "2_2") (pintype "passive"))
      (node (ref "U3") (pin "A1") (pinfunction "VDDQ_1_A1") (pintype "power_in"))
      (node (ref "U3") (pin "A9") (pinfunction "VDDQ_2_A9") (pintype "power_in"))
      (node (ref "U3") (pin "B3") (pinfunction "VDD_1_B3") (pintype "power_in"))
      (node (ref "U3") (pin "B9") (pinfunction "VDD_2_B9") (pintype "power_in"))
      (node (ref "U3") (pin "C1") (pinfunction "VDDQ_3_C1") (pintype "power_in"))
      (node (ref "U3") (pin "D1") (pinfunction "VDD_3_D1") (pintype "power_in"))
      (node (ref "U3") (pin "D9") (pinfunction "VDDQ_4_D9") (pintype "power_in"))
      (node (ref "U3") (pin "F2") (pinfunction "VDDQ_5_F2") (pintype "power_in"))
      (node (ref "U3") (pin "F8") (pinfunction "VDDQ_6_F8") (pintype "power_in"))
      (node (ref "U3") (pin "G1") (pinfunction "VDDQ_7_G1") (pintype "power_in"))
      (node (ref "U3") (pin "G7") (pinfunction "VDD_4_G7") (pintype "power_in"))
      (node (ref "U3") (pin "G9") (pinfunction "VDDQ_8_G9") (pintype "power_in"))
      (node (ref "U3") (pin "J1") (pinfunction "VDD_5_J1") (pintype "power_in"))
      (node (ref "U3") (pin "J2") (pinfunction "VDDQ_9_J2") (pintype "power_in"))
      (node (ref "U3") (pin "J8") (pinfunction "VDDQ_10_J8") (pintype "power_in"))
      (node (ref "U3") (pin "J9") (pinfunction "VDD_6_J9") (pintype "power_in"))
      (node (ref "U3") (pin "L1") (pinfunction "VDD_7_L1") (pintype "power_in"))
      (node (ref "U3") (pin "L9") (pinfunction "VDD_8_L9") (pintype "power_in"))
      (node (ref "U3") (pin "R1") (pinfunction "VDD_9_R1") (pintype "power_in"))
      (node (ref "U3") (pin "T9") (pinfunction "VDD_10_T9") (pintype "power_in"))
      (node (ref "U4") (pin "A1") (pinfunction "VDDQ_1_A1") (pintype "power_in"))
      (node (ref "U4") (pin "A9") (pinfunction "VDDQ_2_A9") (pintype "power_in"))
      (node (ref "U4") (pin "B3") (pinfunction "VDD_1_B3") (pintype "power_in"))
      (node (ref "U4") (pin "B9") (pinfunction "VDD_2_B9") (pintype "power_in"))
      (node (ref "U4") (pin "C1") (pinfunction "VDDQ_3_C1") (pintype "power_in"))
      (node (ref "U4") (pin "D1") (pinfunction "VDD_3_D1") (pintype "power_in"))
      (node (ref "U4") (pin "D9") (pinfunction "VDDQ_4_D9") (pintype "power_in"))
      (node (ref "U4") (pin "F2") (pinfunction "VDDQ_5_F2") (pintype "power_in"))
      (node (ref "U4") (pin "F8") (pinfunction "VDDQ_6_F8") (pintype "power_in"))
      (node (ref "U4") (pin "G1") (pinfunction "VDDQ_7_G1") (pintype "power_in"))
      (node (ref "U4") (pin "G7") (pinfunction "VDD_4_G7") (pintype "power_in"))
      (node (ref "U4") (pin "G9") (pinfunction "VDDQ_8_G9") (pintype "power_in"))
      (node (ref "U4") (pin "J1") (pinfunction "VDD_5_J1") (pintype "power_in"))
      (node (ref "U4") (pin "J2") (pinfunction "VDDQ_9_J2") (pintype "power_in"))
      (node (ref "U4") (pin "J8") (pinfunction "VDDQ_10_J8") (pintype "power_in"))
      (node (ref "U4") (pin "J9") (pinfunction "VDD_6_J9") (pintype "power_in"))
      (node (ref "U4") (pin "L1") (pinfunction "VDD_7_L1") (pintype "power_in"))
      (node (ref "U4") (pin "L9") (pinfunction "VDD_8_L9") (pintype "power_in"))
      (node (ref "U4") (pin "R1") (pinfunction "VDD_9_R1") (pintype "power_in"))
      (node (ref "U4") (pin "T9") (pinfunction "VDD_10_T9") (pintype "power_in"))
    )
    (net (code "84") (name "VCC_SYS") (class "Default")
      (node (ref "C93") (pin "1") (pinfunction "1_1") (pintype "passive"))
      (node (ref "R26") (pin "2") (pinfunction "2_2") (pintype "passive"))
      (node (ref "U5") (pin "1") (pinfunction "VIN_1") (pintype "power_in"))
    )
    (net (code "85") (name "VREF_DDR4_CA") (class "Default")
      (node (ref "C129") (pin "1") (pinfunction "1_1") (pintype "passive"))
      (node (ref "C130") (pin "1") (pinfunction "1_1") (pintype "passive"))
      (node (ref "R27") (pin "1") (pinfunction "1_1") (pintype "passive"))
      (node (ref "R28") (pin "1") (pinfunction "1_1") (pintype "passive"))
      (node (ref "U3") (pin "M1") (pinfunction "VREFCA_M1") (pintype "power_in"))
      (node (ref "U4") (pin "M1") (pinfunction "VREFCA_M1") (pintype "power_in"))
    )
    (net (code "86") (name "unconnected-(U3-ALERT_N-PadP9)") (class "Default")
      (node (ref "U3") (pin "P9") (pinfunction "ALERT_N_P9") (pintype "passive+no_connect"))
    )
    (net (code "87") (name "unconnected-(U3-NC-PadT7)") (class "Default")
      (node (ref "U3") (pin "T7") (pinfunction "NC_T7") (pintype "passive+no_connect"))
    )
    (net (code "88") (name "unconnected-(U3-PAR-PadT3)") (class "Default")
      (node (ref "U3") (pin "T3") (pinfunction "PAR_T3") (pintype "passive+no_connect"))
    )
    (net (code "89") (name "unconnected-(U3-TEN-PadN9)") (class "Default")
      (node (ref "U3") (pin "N9") (pinfunction "TEN_N9") (pintype "passive+no_connect"))
    )
    (net (code "90") (name "unconnected-(U4-ALERT_N-PadP9)") (class "Default")
      (node (ref "U4") (pin "P9") (pinfunction "ALERT_N_P9") (pintype "passive+no_connect"))
    )
    (net (code "91") (name "unconnected-(U4-NC-PadT7)") (class "Default")
      (node (ref "U4") (pin "T7") (pinfunction "NC_T7") (pintype "passive+no_connect"))
    )
    (net (code "92") (name "unconnected-(U4-PAR-PadT3)") (class "Default")
      (node (ref "U4") (pin "T3") (pinfunction "PAR_T3") (pintype "passive+no_connect"))
    )
    (net (code "93") (name "unconnected-(U4-TEN-PadN9)") (class "Default")
      (node (ref "U4") (pin "N9") (pinfunction "TEN_N9") (pintype "passive+no_connect"))
    )
  )
)
